# IMU_v2_module.net
KiCad netlist of a schematic drawn in EAGLE
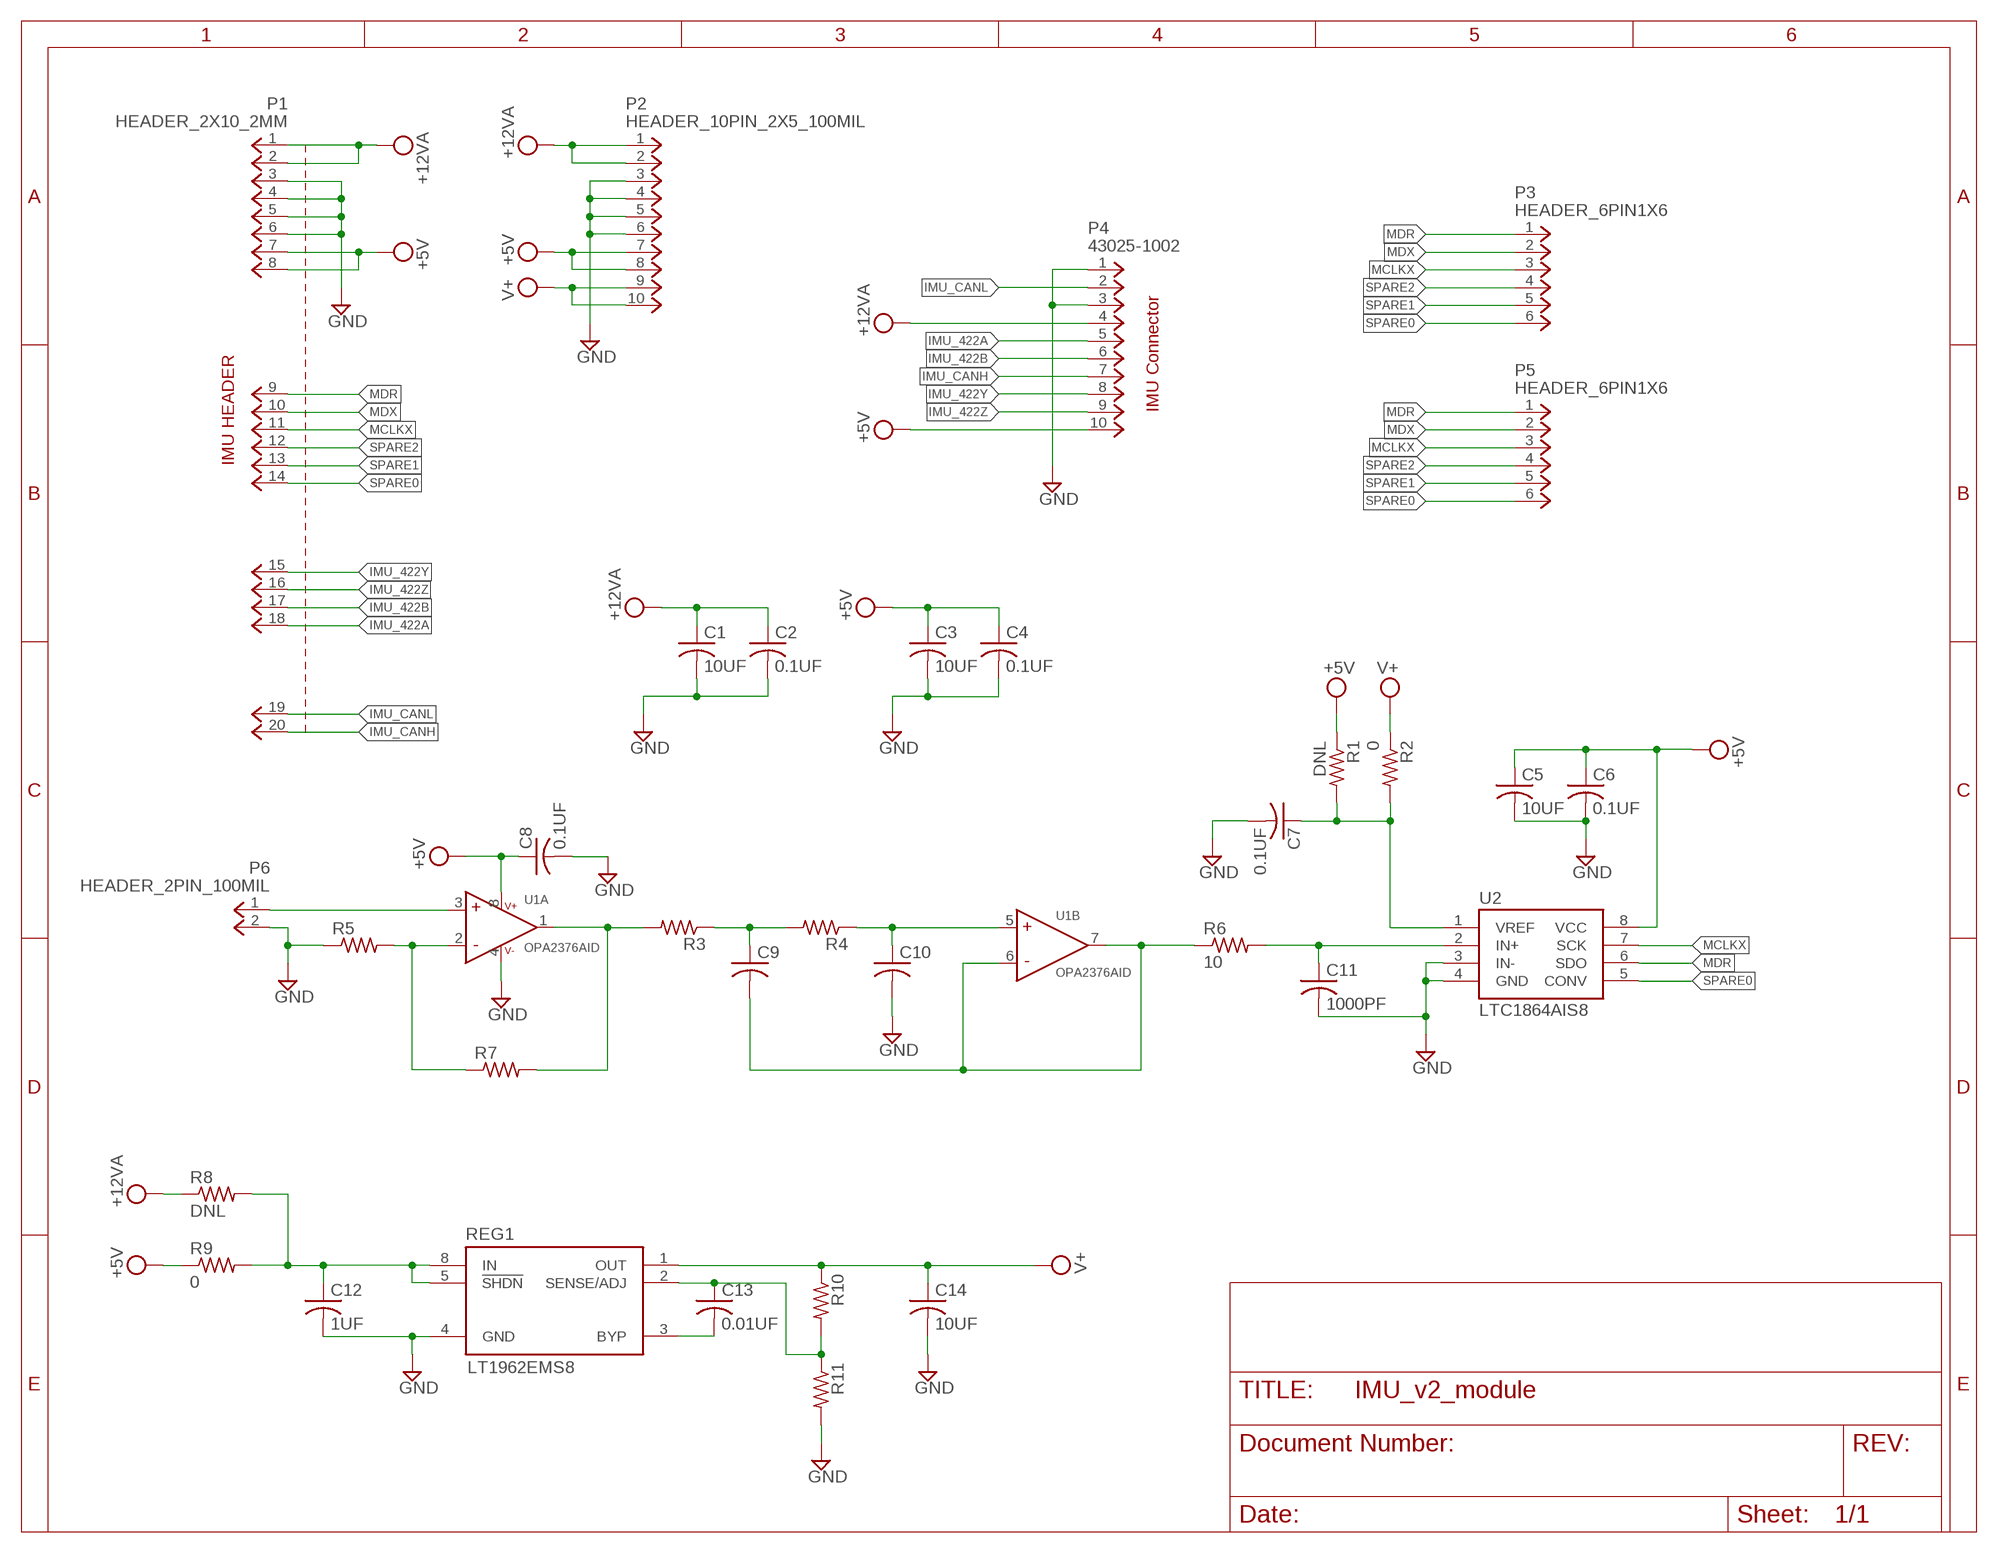
[diagram p0: schematic, sheet 1]

(export (version "E")
  (design (tool "Eeschema 10.0.6"))
  (components
    (comp (ref "C1")
      (value "10UF")
      (footprint "eagle-import:C1206K")
      (libsource (lib "eagle-import") (part "C-USC1206K"))
    )
    (comp (ref "C2")
      (value "0.1UF")
      (footprint "eagle-import:C0603K")
      (libsource (lib "eagle-import") (part "C-USC0603K"))
    )
    (comp (ref "C3")
      (value "10UF")
      (footprint "eagle-import:C1206K")
      (libsource (lib "eagle-import") (part "C-USC1206K"))
    )
    (comp (ref "C4")
      (value "0.1UF")
      (footprint "eagle-import:C0603K")
      (libsource (lib "eagle-import") (part "C-USC0603K"))
    )
    (comp (ref "C5")
      (value "10UF")
      (footprint "eagle-import:C1206")
      (libsource (lib "eagle-import") (part "C-USC1206"))
    )
    (comp (ref "C6")
      (value "0.1UF")
      (footprint "eagle-import:C0603K")
      (libsource (lib "eagle-import") (part "C-USC0603K"))
    )
    (comp (ref "C7")
      (value "0.1UF")
      (footprint "eagle-import:C0603K")
      (libsource (lib "eagle-import") (part "C-USC0603K"))
    )
    (comp (ref "C8")
      (value "0.1UF")
      (footprint "eagle-import:C0603K")
      (libsource (lib "eagle-import") (part "C-USC0603K"))
    )
    (comp (ref "C9")
      (value "C-USC0603K")
      (footprint "eagle-import:C0603K")
      (libsource (lib "eagle-import") (part "C-USC0603K"))
    )
    (comp (ref "C10")
      (value "C-USC0603K")
      (footprint "eagle-import:C0603K")
      (libsource (lib "eagle-import") (part "C-USC0603K"))
    )
    (comp (ref "C11")
      (value "1000PF")
      (footprint "eagle-import:C0603K")
      (libsource (lib "eagle-import") (part "C-USC0603K"))
    )
    (comp (ref "C12")
      (value "1UF")
      (footprint "eagle-import:C0603K")
      (libsource (lib "eagle-import") (part "C-USC0603K"))
    )
    (comp (ref "C13")
      (value "0.01UF")
      (footprint "eagle-import:C0603K")
      (libsource (lib "eagle-import") (part "C-USC0603K"))
    )
    (comp (ref "C14")
      (value "10UF")
      (footprint "eagle-import:C1206K")
      (libsource (lib "eagle-import") (part "C-USC1206K"))
    )
    (comp (ref "P1")
      (value "HEADER_2X10_2MM")
      (footprint "eagle-import:HEADER_2X10_2MM")
      (libsource (lib "eagle-import") (part "HEADER_2X10_2MM"))
    )
    (comp (ref "P2")
      (value "HEADER_10PIN_2X5_100MIL")
      (footprint "eagle-import:HEADER_2X5")
      (libsource (lib "eagle-import") (part "HEADER_10PIN_2X5_100MIL"))
    )
    (comp (ref "P3")
      (value "HEADER_6PIN1X6")
      (footprint "eagle-import:HEADER_1X6")
      (libsource (lib "eagle-import") (part "HEADER_6PIN1X6"))
    )
    (comp (ref "P4")
      (value "43025-1002")
      (footprint "eagle-import:MICRO-FIT_10RA")
      (libsource (lib "eagle-import") (part "43025-1002"))
    )
    (comp (ref "P5")
      (value "HEADER_6PIN1X6")
      (footprint "eagle-import:HEADER_1X6")
      (libsource (lib "eagle-import") (part "HEADER_6PIN1X6"))
    )
    (comp (ref "P6")
      (value "HEADER_2PIN_100MIL")
      (footprint "eagle-import:HEADER_1X2")
      (libsource (lib "eagle-import") (part "HEADER_2PIN_100MIL"))
    )
    (comp (ref "R1")
      (value "DNL")
      (footprint "eagle-import:R0603")
      (libsource (lib "eagle-import") (part "R-US_R0603"))
    )
    (comp (ref "R2")
      (value "0")
      (footprint "eagle-import:R0603")
      (libsource (lib "eagle-import") (part "R-US_R0603"))
    )
    (comp (ref "R3")
      (value "R-US_R0603")
      (footprint "eagle-import:R0603")
      (libsource (lib "eagle-import") (part "R-US_R0603"))
    )
    (comp (ref "R4")
      (value "R-US_R0603")
      (footprint "eagle-import:R0603")
      (libsource (lib "eagle-import") (part "R-US_R0603"))
    )
    (comp (ref "R5")
      (value "R-US_R0603")
      (footprint "eagle-import:R0603")
      (libsource (lib "eagle-import") (part "R-US_R0603"))
    )
    (comp (ref "R6")
      (value "10")
      (footprint "eagle-import:R0603")
      (libsource (lib "eagle-import") (part "R-US_R0603"))
    )
    (comp (ref "R7")
      (value "R-US_R0603")
      (footprint "eagle-import:R0603")
      (libsource (lib "eagle-import") (part "R-US_R0603"))
    )
    (comp (ref "R8")
      (value "DNL")
      (footprint "eagle-import:R0603")
      (libsource (lib "eagle-import") (part "R-US_R0603"))
    )
    (comp (ref "R9")
      (value "0")
      (footprint "eagle-import:R0603")
      (libsource (lib "eagle-import") (part "R-US_R0603"))
    )
    (comp (ref "R10")
      (value "R-US_R0603")
      (footprint "eagle-import:R0603")
      (libsource (lib "eagle-import") (part "R-US_R0603"))
    )
    (comp (ref "R11")
      (value "R-US_R0603")
      (footprint "eagle-import:R0603")
      (libsource (lib "eagle-import") (part "R-US_R0603"))
    )
    (comp (ref "REG1")
      (value "LT1962EMS8")
      (footprint "eagle-import:MSOP8")
      (libsource (lib "eagle-import") (part "LT162EMS89"))
    )
    (comp (ref "U1")
      (value "OPA2376AID")
      (footprint "eagle-import:SOIC8")
      (libsource (lib "eagle-import") (part "OPA2376AID"))
    )
    (comp (ref "U2")
      (value "LTC1864AIS8")
      (footprint "eagle-import:SOIC8")
      (libsource (lib "eagle-import") (part "LTC1864AIS8"))
    )
  )
  (nets
    (net (code "1") (name "+5V") (class "Default")
      (node (ref "C3") (pin "1") (pinfunction "1_1") (pintype "passive"))
      (node (ref "C4") (pin "1") (pinfunction "1_1") (pintype "passive"))
      (node (ref "C5") (pin "1") (pinfunction "1_1") (pintype "passive"))
      (node (ref "C6") (pin "1") (pinfunction "1_1") (pintype "passive"))
      (node (ref "C8") (pin "1") (pinfunction "1_1") (pintype "passive"))
      (node (ref "P1") (pin "7") (pinfunction "1_7") (pintype "bidirectional"))
      (node (ref "P1") (pin "8") (pinfunction "1_8") (pintype "bidirectional"))
      (node (ref "P2") (pin "7") (pinfunction "1_7") (pintype "bidirectional"))
      (node (ref "P2") (pin "8") (pinfunction "1_8") (pintype "bidirectional"))
      (node (ref "P4") (pin "10") (pinfunction "1_10") (pintype "bidirectional"))
      (node (ref "R1") (pin "1") (pinfunction "1_1") (pintype "passive"))
      (node (ref "R9") (pin "1") (pinfunction "1_1") (pintype "passive"))
      (node (ref "U1") (pin "8") (pinfunction "V+_8") (pintype "power_in"))
      (node (ref "U2") (pin "8") (pinfunction "VCC_8") (pintype "power_in"))
    )
    (net (code "2") (name "+12VA") (class "Default")
      (node (ref "C1") (pin "1") (pinfunction "1_1") (pintype "passive"))
      (node (ref "C2") (pin "1") (pinfunction "1_1") (pintype "passive"))
      (node (ref "P1") (pin "1") (pinfunction "1_1") (pintype "bidirectional"))
      (node (ref "P1") (pin "2") (pinfunction "1_2") (pintype "bidirectional"))
      (node (ref "P2") (pin "1") (pinfunction "1_1") (pintype "bidirectional"))
      (node (ref "P2") (pin "2") (pinfunction "1_2") (pintype "bidirectional"))
      (node (ref "P4") (pin "4") (pinfunction "1_4") (pintype "bidirectional"))
      (node (ref "R8") (pin "1") (pinfunction "1_1") (pintype "passive"))
    )
    (net (code "3") (name "GND") (class "Default")
      (node (ref "C1") (pin "2") (pinfunction "2_2") (pintype "passive"))
      (node (ref "C10") (pin "2") (pinfunction "2_2") (pintype "passive"))
      (node (ref "C11") (pin "2") (pinfunction "2_2") (pintype "passive"))
      (node (ref "C12") (pin "2") (pinfunction "2_2") (pintype "passive"))
      (node (ref "C14") (pin "2") (pinfunction "2_2") (pintype "passive"))
      (node (ref "C2") (pin "2") (pinfunction "2_2") (pintype "passive"))
      (node (ref "C3") (pin "2") (pinfunction "2_2") (pintype "passive"))
      (node (ref "C4") (pin "2") (pinfunction "2_2") (pintype "passive"))
      (node (ref "C5") (pin "2") (pinfunction "2_2") (pintype "passive"))
      (node (ref "C6") (pin "2") (pinfunction "2_2") (pintype "passive"))
      (node (ref "C7") (pin "2") (pinfunction "2_2") (pintype "passive"))
      (node (ref "C8") (pin "2") (pinfunction "2_2") (pintype "passive"))
      (node (ref "P1") (pin "3") (pinfunction "1_3") (pintype "bidirectional"))
      (node (ref "P1") (pin "4") (pinfunction "1_4") (pintype "bidirectional"))
      (node (ref "P1") (pin "5") (pinfunction "1_5") (pintype "bidirectional"))
      (node (ref "P1") (pin "6") (pinfunction "1_6") (pintype "bidirectional"))
      (node (ref "P2") (pin "3") (pinfunction "1_3") (pintype "bidirectional"))
      (node (ref "P2") (pin "4") (pinfunction "1_4") (pintype "bidirectional"))
      (node (ref "P2") (pin "5") (pinfunction "1_5") (pintype "bidirectional"))
      (node (ref "P2") (pin "6") (pinfunction "1_6") (pintype "bidirectional"))
      (node (ref "P4") (pin "1") (pinfunction "1_1") (pintype "bidirectional"))
      (node (ref "P4") (pin "3") (pinfunction "1_3") (pintype "bidirectional"))
      (node (ref "P6") (pin "2") (pinfunction "1_2") (pintype "bidirectional"))
      (node (ref "R11") (pin "2") (pinfunction "2_2") (pintype "passive"))
      (node (ref "R5") (pin "1") (pinfunction "1_1") (pintype "passive"))
      (node (ref "REG1") (pin "4") (pinfunction "GND_4") (pintype "power_in"))
      (node (ref "U1") (pin "4") (pinfunction "V-_4") (pintype "power_in"))
      (node (ref "U2") (pin "3") (pinfunction "IN-_3") (pintype "input"))
      (node (ref "U2") (pin "4") (pinfunction "GND_4") (pintype "power_in"))
    )
    (net (code "4") (name "IMU_422A") (class "Default")
      (node (ref "P1") (pin "18") (pinfunction "1_18") (pintype "bidirectional"))
      (node (ref "P4") (pin "5") (pinfunction "1_5") (pintype "bidirectional"))
    )
    (net (code "5") (name "IMU_422B") (class "Default")
      (node (ref "P1") (pin "17") (pinfunction "1_17") (pintype "bidirectional"))
      (node (ref "P4") (pin "6") (pinfunction "1_6") (pintype "bidirectional"))
    )
    (net (code "6") (name "IMU_422Y") (class "Default")
      (node (ref "P1") (pin "15") (pinfunction "1_15") (pintype "bidirectional"))
      (node (ref "P4") (pin "8") (pinfunction "1_8") (pintype "bidirectional"))
    )
    (net (code "7") (name "IMU_422Z") (class "Default")
      (node (ref "P1") (pin "16") (pinfunction "1_16") (pintype "bidirectional"))
      (node (ref "P4") (pin "9") (pinfunction "1_9") (pintype "bidirectional"))
    )
    (net (code "8") (name "IMU_CANH") (class "Default")
      (node (ref "P1") (pin "20") (pinfunction "1_20") (pintype "bidirectional"))
      (node (ref "P4") (pin "7") (pinfunction "1_7") (pintype "bidirectional"))
    )
    (net (code "9") (name "IMU_CANL") (class "Default")
      (node (ref "P1") (pin "19") (pinfunction "1_19") (pintype "bidirectional"))
      (node (ref "P4") (pin "2") (pinfunction "1_2") (pintype "bidirectional"))
    )
    (net (code "10") (name "MCLKX") (class "Default")
      (node (ref "P1") (pin "11") (pinfunction "1_11") (pintype "bidirectional"))
      (node (ref "P3") (pin "3") (pinfunction "1_3") (pintype "bidirectional"))
      (node (ref "P5") (pin "3") (pinfunction "1_3") (pintype "bidirectional"))
      (node (ref "U2") (pin "7") (pinfunction "SCK_7") (pintype "input"))
    )
    (net (code "11") (name "MDR") (class "Default")
      (node (ref "P1") (pin "9") (pinfunction "1_9") (pintype "bidirectional"))
      (node (ref "P3") (pin "1") (pinfunction "1_1") (pintype "bidirectional"))
      (node (ref "P5") (pin "1") (pinfunction "1_1") (pintype "bidirectional"))
      (node (ref "U2") (pin "6") (pinfunction "SDO_6") (pintype "output"))
    )
    (net (code "12") (name "MDX") (class "Default")
      (node (ref "P1") (pin "10") (pinfunction "1_10") (pintype "bidirectional"))
      (node (ref "P3") (pin "2") (pinfunction "1_2") (pintype "bidirectional"))
      (node (ref "P5") (pin "2") (pinfunction "1_2") (pintype "bidirectional"))
    )
    (net (code "13") (name "Net-(C9-Pad1)") (class "Default")
      (node (ref "C9") (pin "1") (pinfunction "1_1") (pintype "passive"))
      (node (ref "R3") (pin "1") (pinfunction "1_1") (pintype "passive"))
      (node (ref "R4") (pin "2") (pinfunction "2_2") (pintype "passive"))
    )
    (net (code "14") (name "Net-(REG1-BYP)") (class "Default")
      (node (ref "C13") (pin "2") (pinfunction "2_2") (pintype "passive"))
      (node (ref "REG1") (pin "3") (pinfunction "BYP_3") (pintype "input"))
    )
    (net (code "15") (name "Net-(REG1-IN)") (class "Default")
      (node (ref "C12") (pin "1") (pinfunction "1_1") (pintype "passive"))
      (node (ref "R8") (pin "2") (pinfunction "2_2") (pintype "passive"))
      (node (ref "R9") (pin "2") (pinfunction "2_2") (pintype "passive"))
      (node (ref "REG1") (pin "5") (pinfunction "~{SHDN}_5") (pintype "input"))
      (node (ref "REG1") (pin "8") (pinfunction "IN_8") (pintype "power_in"))
    )
    (net (code "16") (name "Net-(REG1-SENSE{slash}ADJ)") (class "Default")
      (node (ref "C13") (pin "1") (pinfunction "1_1") (pintype "passive"))
      (node (ref "R10") (pin "2") (pinfunction "2_2") (pintype "passive"))
      (node (ref "R11") (pin "1") (pinfunction "1_1") (pintype "passive"))
      (node (ref "REG1") (pin "2") (pinfunction "SENSE/ADJ_2") (pintype "input"))
    )
    (net (code "17") (name "Net-(U1A-IN+)") (class "Default")
      (node (ref "P6") (pin "1") (pinfunction "1_1") (pintype "bidirectional"))
      (node (ref "U1") (pin "3") (pinfunction "IN+_3") (pintype "input"))
    )
    (net (code "18") (name "Net-(U1A-IN-)") (class "Default")
      (node (ref "R5") (pin "2") (pinfunction "2_2") (pintype "passive"))
      (node (ref "R7") (pin "1") (pinfunction "1_1") (pintype "passive"))
      (node (ref "U1") (pin "2") (pinfunction "IN-_2") (pintype "input"))
    )
    (net (code "19") (name "Net-(U1A-OUT)") (class "Default")
      (node (ref "R3") (pin "2") (pinfunction "2_2") (pintype "passive"))
      (node (ref "R7") (pin "2") (pinfunction "2_2") (pintype "passive"))
      (node (ref "U1") (pin "1") (pinfunction "OUT_1") (pintype "output"))
    )
    (net (code "20") (name "Net-(U1B-IN+)") (class "Default")
      (node (ref "C10") (pin "1") (pinfunction "1_1") (pintype "passive"))
      (node (ref "R4") (pin "1") (pinfunction "1_1") (pintype "passive"))
      (node (ref "U1") (pin "5") (pinfunction "IN+_5") (pintype "input"))
    )
    (net (code "21") (name "Net-(U1B-IN-)") (class "Default")
      (node (ref "C9") (pin "2") (pinfunction "2_2") (pintype "passive"))
      (node (ref "R6") (pin "1") (pinfunction "1_1") (pintype "passive"))
      (node (ref "U1") (pin "6") (pinfunction "IN-_6") (pintype "input"))
      (node (ref "U1") (pin "7") (pinfunction "OUT_7") (pintype "output"))
    )
    (net (code "22") (name "Net-(U2-IN+)") (class "Default")
      (node (ref "C11") (pin "1") (pinfunction "1_1") (pintype "passive"))
      (node (ref "R6") (pin "2") (pinfunction "2_2") (pintype "passive"))
      (node (ref "U2") (pin "2") (pinfunction "IN+_2") (pintype "input"))
    )
    (net (code "23") (name "Net-(U2-VREF)") (class "Default")
      (node (ref "C7") (pin "1") (pinfunction "1_1") (pintype "passive"))
      (node (ref "R1") (pin "2") (pinfunction "2_2") (pintype "passive"))
      (node (ref "R2") (pin "2") (pinfunction "2_2") (pintype "passive"))
      (node (ref "U2") (pin "1") (pinfunction "VREF_1") (pintype "input"))
    )
    (net (code "24") (name "SPARE0") (class "Default")
      (node (ref "P1") (pin "14") (pinfunction "1_14") (pintype "bidirectional"))
      (node (ref "P3") (pin "6") (pinfunction "1_6") (pintype "bidirectional"))
      (node (ref "P5") (pin "6") (pinfunction "1_6") (pintype "bidirectional"))
      (node (ref "U2") (pin "5") (pinfunction "CONV_5") (pintype "input"))
    )
    (net (code "25") (name "SPARE1") (class "Default")
      (node (ref "P1") (pin "13") (pinfunction "1_13") (pintype "bidirectional"))
      (node (ref "P3") (pin "5") (pinfunction "1_5") (pintype "bidirectional"))
      (node (ref "P5") (pin "5") (pinfunction "1_5") (pintype "bidirectional"))
    )
    (net (code "26") (name "SPARE2") (class "Default")
      (node (ref "P1") (pin "12") (pinfunction "1_12") (pintype "bidirectional"))
      (node (ref "P3") (pin "4") (pinfunction "1_4") (pintype "bidirectional"))
      (node (ref "P5") (pin "4") (pinfunction "1_4") (pintype "bidirectional"))
    )
    (net (code "27") (name "V+") (class "Default")
      (node (ref "C14") (pin "1") (pinfunction "1_1") (pintype "passive"))
      (node (ref "P2") (pin "10") (pinfunction "1_10") (pintype "bidirectional"))
      (node (ref "P2") (pin "9") (pinfunction "1_9") (pintype "bidirectional"))
      (node (ref "R10") (pin "1") (pinfunction "1_1") (pintype "passive"))
      (node (ref "R2") (pin "1") (pinfunction "1_1") (pintype "passive"))
      (node (ref "REG1") (pin "1") (pinfunction "OUT_1") (pintype "power_in"))
    )
  )
)
